# 3port-PicoUPS.net
KiCad netlist of a schematic drawn in EAGLE
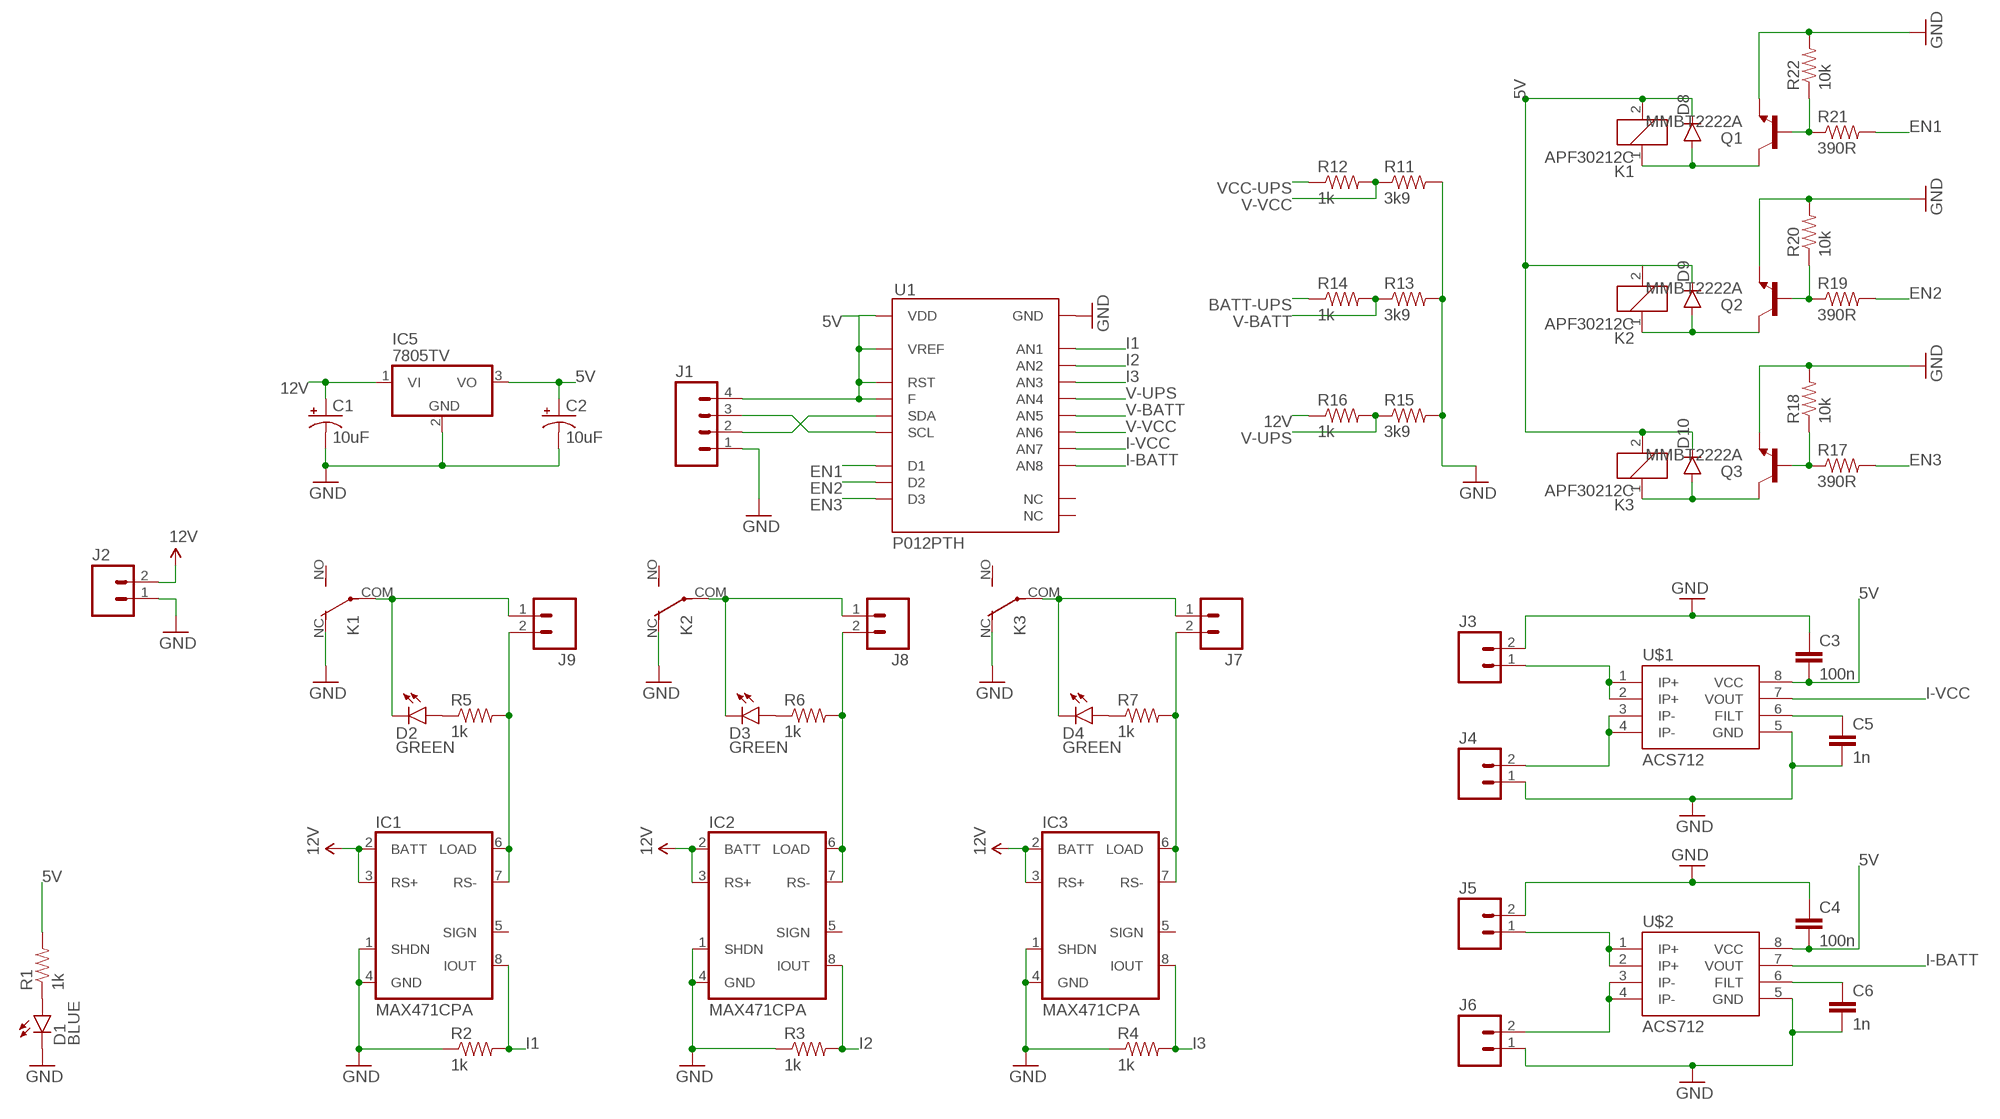
[diagram p0: schematic, sheet 1]

(export (version "E")
  (design (tool "Eeschema 10.0.6"))
  (components
    (comp (ref "C1")
      (value "10uF")
      (footprint "eagle-import:EIA3216")
      (libsource (lib "eagle-import") (part "10UF-16V-10%(TANT)"))
    )
    (comp (ref "C2")
      (value "10uF")
      (footprint "eagle-import:EIA3216")
      (libsource (lib "eagle-import") (part "10UF-16V-10%(TANT)"))
    )
    (comp (ref "C3")
      (value "100n")
      (footprint "eagle-import:0805")
      (libsource (lib "eagle-import") (part "CAP0805"))
    )
    (comp (ref "C4")
      (value "100n")
      (footprint "eagle-import:0805")
      (libsource (lib "eagle-import") (part "CAP0805"))
    )
    (comp (ref "C5")
      (value "1n")
      (footprint "eagle-import:0805")
      (libsource (lib "eagle-import") (part "CAP0805"))
    )
    (comp (ref "C6")
      (value "1n")
      (footprint "eagle-import:0805")
      (libsource (lib "eagle-import") (part "CAP0805"))
    )
    (comp (ref "D1")
      (value "BLUE")
      (footprint "eagle-import:LED-0603")
      (libsource (lib "eagle-import") (part "LED-BLUE0603"))
    )
    (comp (ref "D2")
      (value "GREEN")
      (footprint "eagle-import:LED-0603")
      (libsource (lib "eagle-import") (part "LED-GREEN0603"))
    )
    (comp (ref "D3")
      (value "GREEN")
      (footprint "eagle-import:LED-0603")
      (libsource (lib "eagle-import") (part "LED-GREEN0603"))
    )
    (comp (ref "D4")
      (value "GREEN")
      (footprint "eagle-import:LED-0603")
      (libsource (lib "eagle-import") (part "LED-GREEN0603"))
    )
    (comp (ref "D8")
      (value "DIODESOD123")
      (footprint "eagle-import:SOD-123")
      (libsource (lib "eagle-import") (part "DIODESOD123"))
    )
    (comp (ref "D9")
      (value "DIODESOD123")
      (footprint "eagle-import:SOD-123")
      (libsource (lib "eagle-import") (part "DIODESOD123"))
    )
    (comp (ref "D10")
      (value "DIODESOD123")
      (footprint "eagle-import:SOD-123")
      (libsource (lib "eagle-import") (part "DIODESOD123"))
    )
    (comp (ref "IC1")
      (value "MAX471CPA")
      (footprint "eagle-import:SO08")
      (libsource (lib "eagle-import") (part "MAX471CPA"))
    )
    (comp (ref "IC2")
      (value "MAX471CPA")
      (footprint "eagle-import:SO08")
      (libsource (lib "eagle-import") (part "MAX471CPA"))
    )
    (comp (ref "IC3")
      (value "MAX471CPA")
      (footprint "eagle-import:SO08")
      (libsource (lib "eagle-import") (part "MAX471CPA"))
    )
    (comp (ref "IC5")
      (value "7805TV")
      (footprint "eagle-import:TO220V")
      (libsource (lib "eagle-import") (part "78TV05"))
    )
    (comp (ref "J1")
      (value "M04PTH")
      (footprint "eagle-import:1X04")
      (libsource (lib "eagle-import") (part "M04PTH"))
    )
    (comp (ref "J2")
      (value "M025MM")
      (footprint "eagle-import:SCREWTERMINAL-5MM-2")
      (libsource (lib "eagle-import") (part "M025MM"))
    )
    (comp (ref "J3")
      (value "M025MM")
      (footprint "eagle-import:SCREWTERMINAL-5MM-2")
      (libsource (lib "eagle-import") (part "M025MM"))
    )
    (comp (ref "J4")
      (value "M025MM")
      (footprint "eagle-import:SCREWTERMINAL-5MM-2")
      (libsource (lib "eagle-import") (part "M025MM"))
    )
    (comp (ref "J5")
      (value "M025MM")
      (footprint "eagle-import:SCREWTERMINAL-5MM-2")
      (libsource (lib "eagle-import") (part "M025MM"))
    )
    (comp (ref "J6")
      (value "M025MM")
      (footprint "eagle-import:SCREWTERMINAL-5MM-2")
      (libsource (lib "eagle-import") (part "M025MM"))
    )
    (comp (ref "J7")
      (value "M025MM")
      (footprint "eagle-import:SCREWTERMINAL-5MM-2")
      (libsource (lib "eagle-import") (part "M025MM"))
    )
    (comp (ref "J8")
      (value "M025MM")
      (footprint "eagle-import:SCREWTERMINAL-5MM-2")
      (libsource (lib "eagle-import") (part "M025MM"))
    )
    (comp (ref "J9")
      (value "M025MM")
      (footprint "eagle-import:SCREWTERMINAL-5MM-2")
      (libsource (lib "eagle-import") (part "M025MM"))
    )
    (comp (ref "K1")
      (value "APF30212C")
      (footprint "eagle-import:APF30212C")
      (libsource (lib "eagle-import") (part "APF30212C"))
    )
    (comp (ref "K2")
      (value "APF30212C")
      (footprint "eagle-import:APF30212C")
      (libsource (lib "eagle-import") (part "APF30212C"))
    )
    (comp (ref "K3")
      (value "APF30212C")
      (footprint "eagle-import:APF30212C")
      (libsource (lib "eagle-import") (part "APF30212C"))
    )
    (comp (ref "Q1")
      (value "MMBT2222A")
      (footprint "eagle-import:SOT23-3")
      (libsource (lib "eagle-import") (part "TRANSISTOR_NPNMMBT2222A"))
    )
    (comp (ref "Q2")
      (value "MMBT2222A")
      (footprint "eagle-import:SOT23-3")
      (libsource (lib "eagle-import") (part "TRANSISTOR_NPNMMBT2222A"))
    )
    (comp (ref "Q3")
      (value "MMBT2222A")
      (footprint "eagle-import:SOT23-3")
      (libsource (lib "eagle-import") (part "TRANSISTOR_NPNMMBT2222A"))
    )
    (comp (ref "R1")
      (value "1k")
      (footprint "eagle-import:0805")
      (libsource (lib "eagle-import") (part "RESISTOR0805-RES"))
    )
    (comp (ref "R2")
      (value "1k")
      (footprint "eagle-import:0805")
      (libsource (lib "eagle-import") (part "RESISTOR0805-RES"))
    )
    (comp (ref "R3")
      (value "1k")
      (footprint "eagle-import:0805")
      (libsource (lib "eagle-import") (part "RESISTOR0805-RES"))
    )
    (comp (ref "R4")
      (value "1k")
      (footprint "eagle-import:0805")
      (libsource (lib "eagle-import") (part "RESISTOR0805-RES"))
    )
    (comp (ref "R5")
      (value "1k")
      (footprint "eagle-import:0805")
      (libsource (lib "eagle-import") (part "RESISTOR0805-RES"))
    )
    (comp (ref "R6")
      (value "1k")
      (footprint "eagle-import:0805")
      (libsource (lib "eagle-import") (part "RESISTOR0805-RES"))
    )
    (comp (ref "R7")
      (value "1k")
      (footprint "eagle-import:0805")
      (libsource (lib "eagle-import") (part "RESISTOR0805-RES"))
    )
    (comp (ref "R11")
      (value "3k9")
      (footprint "eagle-import:0805")
      (libsource (lib "eagle-import") (part "RESISTOR0805-RES"))
    )
    (comp (ref "R12")
      (value "1k")
      (footprint "eagle-import:0805")
      (libsource (lib "eagle-import") (part "RESISTOR0805-RES"))
    )
    (comp (ref "R13")
      (value "3k9")
      (footprint "eagle-import:0805")
      (libsource (lib "eagle-import") (part "RESISTOR0805-RES"))
    )
    (comp (ref "R14")
      (value "1k")
      (footprint "eagle-import:0805")
      (libsource (lib "eagle-import") (part "RESISTOR0805-RES"))
    )
    (comp (ref "R15")
      (value "3k9")
      (footprint "eagle-import:0805")
      (libsource (lib "eagle-import") (part "RESISTOR0805-RES"))
    )
    (comp (ref "R16")
      (value "1k")
      (footprint "eagle-import:0805")
      (libsource (lib "eagle-import") (part "RESISTOR0805-RES"))
    )
    (comp (ref "R17")
      (value "390R")
      (footprint "eagle-import:0805")
      (libsource (lib "eagle-import") (part "RESISTOR0805-RES"))
    )
    (comp (ref "R18")
      (value "10k")
      (footprint "eagle-import:0805")
      (libsource (lib "eagle-import") (part "RESISTOR0805-RES"))
    )
    (comp (ref "R19")
      (value "390R")
      (footprint "eagle-import:0805")
      (libsource (lib "eagle-import") (part "RESISTOR0805-RES"))
    )
    (comp (ref "R20")
      (value "10k")
      (footprint "eagle-import:0805")
      (libsource (lib "eagle-import") (part "RESISTOR0805-RES"))
    )
    (comp (ref "R21")
      (value "390R")
      (footprint "eagle-import:0805")
      (libsource (lib "eagle-import") (part "RESISTOR0805-RES"))
    )
    (comp (ref "R22")
      (value "10k")
      (footprint "eagle-import:0805")
      (libsource (lib "eagle-import") (part "RESISTOR0805-RES"))
    )
    (comp (ref "U$1")
      (value "ACS712")
      (footprint "eagle-import:SO08")
      (libsource (lib "eagle-import") (part "ACS712"))
    )
    (comp (ref "U$2")
      (value "ACS712")
      (footprint "eagle-import:SO08")
      (libsource (lib "eagle-import") (part "ACS712"))
    )
    (comp (ref "U1")
      (value "P012PTH")
      (footprint "eagle-import:DIL20")
      (libsource (lib "eagle-import") (part "P012PTH"))
    )
  )
  (nets
    (net (code "1") (name "/5V") (class "Default")
      (node (ref "C2") (pin "A") (pinfunction "+_A") (pintype "passive"))
      (node (ref "C3") (pin "2") (pinfunction "2_2") (pintype "passive"))
      (node (ref "C4") (pin "2") (pinfunction "2_2") (pintype "passive"))
      (node (ref "D10") (pin "C") (pinfunction "C_C") (pintype "passive"))
      (node (ref "D8") (pin "C") (pinfunction "C_C") (pintype "passive"))
      (node (ref "D9") (pin "C") (pinfunction "C_C") (pintype "passive"))
      (node (ref "IC5") (pin "3") (pinfunction "VO_3") (pintype "passive"))
      (node (ref "J1") (pin "4") (pinfunction "4_4") (pintype "passive"))
      (node (ref "K1") (pin "2") (pinfunction "2_2") (pintype "passive"))
      (node (ref "K2") (pin "2") (pinfunction "2_2") (pintype "passive"))
      (node (ref "K3") (pin "2") (pinfunction "2_2") (pintype "passive"))
      (node (ref "R1") (pin "2") (pinfunction "2_2") (pintype "passive"))
      (node (ref "U$1") (pin "8") (pinfunction "VCC_8") (pintype "bidirectional"))
      (node (ref "U$2") (pin "8") (pinfunction "VCC_8") (pintype "bidirectional"))
      (node (ref "U1") (pin "1") (pinfunction "VDD_1") (pintype "power_in"))
      (node (ref "U1") (pin "18") (pinfunction "VREF_18") (pintype "input"))
      (node (ref "U1") (pin "4") (pinfunction "RST_4") (pintype "input"))
      (node (ref "U1") (pin "9") (pinfunction "F_9") (pintype "input"))
    )
    (net (code "2") (name "/BATT-UPS") (class "Default")
      (node (ref "J6") (pin "2") (pinfunction "2_2") (pintype "passive"))
      (node (ref "R14") (pin "1") (pinfunction "1_1") (pintype "passive"))
      (node (ref "U$2") (pin "3") (pinfunction "IP-_3") (pintype "bidirectional"))
      (node (ref "U$2") (pin "4") (pinfunction "IP-_4") (pintype "bidirectional"))
    )
    (net (code "3") (name "/EN1") (class "Default")
      (node (ref "R21") (pin "2") (pinfunction "2_2") (pintype "passive"))
      (node (ref "U1") (pin "2") (pinfunction "D1_2") (pintype "output"))
    )
    (net (code "4") (name "/EN2") (class "Default")
      (node (ref "R19") (pin "2") (pinfunction "2_2") (pintype "passive"))
      (node (ref "U1") (pin "6") (pinfunction "D2_6") (pintype "output"))
    )
    (net (code "5") (name "/EN3") (class "Default")
      (node (ref "R17") (pin "2") (pinfunction "2_2") (pintype "passive"))
      (node (ref "U1") (pin "5") (pinfunction "D3_5") (pintype "output"))
    )
    (net (code "6") (name "/I-BATT") (class "Default")
      (node (ref "U$2") (pin "7") (pinfunction "VOUT_7") (pintype "bidirectional"))
      (node (ref "U1") (pin "19") (pinfunction "AN8_19") (pintype "input"))
    )
    (net (code "7") (name "/I-VCC") (class "Default")
      (node (ref "U$1") (pin "7") (pinfunction "VOUT_7") (pintype "bidirectional"))
      (node (ref "U1") (pin "17") (pinfunction "AN7_17") (pintype "input"))
    )
    (net (code "8") (name "/I1") (class "Default")
      (node (ref "IC1") (pin "8") (pinfunction "IOUT_8") (pintype "output"))
      (node (ref "R2") (pin "2") (pinfunction "2_2") (pintype "passive"))
      (node (ref "U1") (pin "3") (pinfunction "AN1_3") (pintype "input"))
    )
    (net (code "9") (name "/I2") (class "Default")
      (node (ref "IC2") (pin "8") (pinfunction "IOUT_8") (pintype "output"))
      (node (ref "R3") (pin "2") (pinfunction "2_2") (pintype "passive"))
      (node (ref "U1") (pin "7") (pinfunction "AN2_7") (pintype "input"))
    )
    (net (code "10") (name "/I3") (class "Default")
      (node (ref "IC3") (pin "8") (pinfunction "IOUT_8") (pintype "output"))
      (node (ref "R4") (pin "2") (pinfunction "2_2") (pintype "passive"))
      (node (ref "U1") (pin "8") (pinfunction "AN3_8") (pintype "input"))
    )
    (net (code "11") (name "/V-BATT") (class "Default")
      (node (ref "R13") (pin "1") (pinfunction "1_1") (pintype "passive"))
      (node (ref "R14") (pin "2") (pinfunction "2_2") (pintype "passive"))
      (node (ref "U1") (pin "15") (pinfunction "AN5_15") (pintype "input"))
    )
    (net (code "12") (name "/V-UPS") (class "Default")
      (node (ref "R15") (pin "1") (pinfunction "1_1") (pintype "passive"))
      (node (ref "R16") (pin "2") (pinfunction "2_2") (pintype "passive"))
      (node (ref "U1") (pin "14") (pinfunction "AN4_14") (pintype "input"))
    )
    (net (code "13") (name "/V-VCC") (class "Default")
      (node (ref "R11") (pin "1") (pinfunction "1_1") (pintype "passive"))
      (node (ref "R12") (pin "2") (pinfunction "2_2") (pintype "passive"))
      (node (ref "U1") (pin "16") (pinfunction "AN6_16") (pintype "input"))
    )
    (net (code "14") (name "/VCC-UPS") (class "Default")
      (node (ref "J4") (pin "2") (pinfunction "2_2") (pintype "passive"))
      (node (ref "R12") (pin "1") (pinfunction "1_1") (pintype "passive"))
      (node (ref "U$1") (pin "3") (pinfunction "IP-_3") (pintype "bidirectional"))
      (node (ref "U$1") (pin "4") (pinfunction "IP-_4") (pintype "bidirectional"))
    )
    (net (code "15") (name "12V") (class "Default")
      (node (ref "C1") (pin "A") (pinfunction "+_A") (pintype "passive"))
      (node (ref "IC1") (pin "2") (pinfunction "BATT_2") (pintype "input"))
      (node (ref "IC1") (pin "3") (pinfunction "RS+_3") (pintype "input"))
      (node (ref "IC2") (pin "2") (pinfunction "BATT_2") (pintype "input"))
      (node (ref "IC2") (pin "3") (pinfunction "RS+_3") (pintype "input"))
      (node (ref "IC3") (pin "2") (pinfunction "BATT_2") (pintype "input"))
      (node (ref "IC3") (pin "3") (pinfunction "RS+_3") (pintype "input"))
      (node (ref "IC5") (pin "1") (pinfunction "VI_1") (pintype "input"))
      (node (ref "J2") (pin "2") (pinfunction "2_2") (pintype "passive"))
      (node (ref "R16") (pin "1") (pinfunction "1_1") (pintype "passive"))
    )
    (net (code "16") (name "GND") (class "Default")
      (node (ref "C1") (pin "C") (pinfunction "-_C") (pintype "passive"))
      (node (ref "C2") (pin "C") (pinfunction "-_C") (pintype "passive"))
      (node (ref "C3") (pin "1") (pinfunction "1_1") (pintype "passive"))
      (node (ref "C4") (pin "1") (pinfunction "1_1") (pintype "passive"))
      (node (ref "C5") (pin "2") (pinfunction "2_2") (pintype "passive"))
      (node (ref "C6") (pin "2") (pinfunction "2_2") (pintype "passive"))
      (node (ref "D1") (pin "C") (pinfunction "C_C") (pintype "passive"))
      (node (ref "IC1") (pin "1") (pinfunction "SHDN_1") (pintype "input"))
      (node (ref "IC1") (pin "4") (pinfunction "GND_4") (pintype "power_in"))
      (node (ref "IC2") (pin "1") (pinfunction "SHDN_1") (pintype "input"))
      (node (ref "IC2") (pin "4") (pinfunction "GND_4") (pintype "power_in"))
      (node (ref "IC3") (pin "1") (pinfunction "SHDN_1") (pintype "input"))
      (node (ref "IC3") (pin "4") (pinfunction "GND_4") (pintype "power_in"))
      (node (ref "IC5") (pin "2") (pinfunction "GND_2") (pintype "passive"))
      (node (ref "J1") (pin "1") (pinfunction "1_1") (pintype "passive"))
      (node (ref "J2") (pin "1") (pinfunction "1_1") (pintype "passive"))
      (node (ref "J3") (pin "2") (pinfunction "2_2") (pintype "passive"))
      (node (ref "J4") (pin "1") (pinfunction "1_1") (pintype "passive"))
      (node (ref "J5") (pin "2") (pinfunction "2_2") (pintype "passive"))
      (node (ref "J6") (pin "1") (pinfunction "1_1") (pintype "passive"))
      (node (ref "K1") (pin "NC") (pinfunction "O_NC") (pintype "passive"))
      (node (ref "K2") (pin "NC") (pinfunction "O_NC") (pintype "passive"))
      (node (ref "K3") (pin "NC") (pinfunction "O_NC") (pintype "passive"))
      (node (ref "Q1") (pin "2") (pinfunction "E_2") (pintype "passive"))
      (node (ref "Q2") (pin "2") (pinfunction "E_2") (pintype "passive"))
      (node (ref "Q3") (pin "2") (pinfunction "E_2") (pintype "passive"))
      (node (ref "R11") (pin "2") (pinfunction "2_2") (pintype "passive"))
      (node (ref "R13") (pin "2") (pinfunction "2_2") (pintype "passive"))
      (node (ref "R15") (pin "2") (pinfunction "2_2") (pintype "passive"))
      (node (ref "R18") (pin "2") (pinfunction "2_2") (pintype "passive"))
      (node (ref "R2") (pin "1") (pinfunction "1_1") (pintype "passive"))
      (node (ref "R20") (pin "2") (pinfunction "2_2") (pintype "passive"))
      (node (ref "R22") (pin "2") (pinfunction "2_2") (pintype "passive"))
      (node (ref "R3") (pin "1") (pinfunction "1_1") (pintype "passive"))
      (node (ref "R4") (pin "1") (pinfunction "1_1") (pintype "passive"))
      (node (ref "U$1") (pin "5") (pinfunction "GND_5") (pintype "bidirectional"))
      (node (ref "U$2") (pin "5") (pinfunction "GND_5") (pintype "bidirectional"))
      (node (ref "U1") (pin "20") (pinfunction "GND_20") (pintype "power_in"))
    )
    (net (code "17") (name "Net-(D1-PadA)") (class "Default")
      (node (ref "D1") (pin "A") (pinfunction "A_A") (pintype "passive"))
      (node (ref "R1") (pin "1") (pinfunction "1_1") (pintype "passive"))
    )
    (net (code "18") (name "Net-(D2-PadA)") (class "Default")
      (node (ref "D2") (pin "A") (pinfunction "A_A") (pintype "passive"))
      (node (ref "R5") (pin "1") (pinfunction "1_1") (pintype "passive"))
    )
    (net (code "19") (name "Net-(D3-PadA)") (class "Default")
      (node (ref "D3") (pin "A") (pinfunction "A_A") (pintype "passive"))
      (node (ref "R6") (pin "1") (pinfunction "1_1") (pintype "passive"))
    )
    (net (code "20") (name "Net-(D4-PadA)") (class "Default")
      (node (ref "D4") (pin "A") (pinfunction "A_A") (pintype "passive"))
      (node (ref "R7") (pin "1") (pinfunction "1_1") (pintype "passive"))
    )
    (net (code "21") (name "Net-(IC1-LOAD)") (class "Default")
      (node (ref "IC1") (pin "6") (pinfunction "LOAD_6") (pintype "output"))
      (node (ref "IC1") (pin "7") (pinfunction "RS-_7") (pintype "input"))
      (node (ref "J9") (pin "2") (pinfunction "2_2") (pintype "passive"))
      (node (ref "R5") (pin "2") (pinfunction "2_2") (pintype "passive"))
    )
    (net (code "22") (name "Net-(IC2-LOAD)") (class "Default")
      (node (ref "IC2") (pin "6") (pinfunction "LOAD_6") (pintype "output"))
      (node (ref "IC2") (pin "7") (pinfunction "RS-_7") (pintype "input"))
      (node (ref "J8") (pin "2") (pinfunction "2_2") (pintype "passive"))
      (node (ref "R6") (pin "2") (pinfunction "2_2") (pintype "passive"))
    )
    (net (code "23") (name "Net-(IC3-LOAD)") (class "Default")
      (node (ref "IC3") (pin "6") (pinfunction "LOAD_6") (pintype "output"))
      (node (ref "IC3") (pin "7") (pinfunction "RS-_7") (pintype "input"))
      (node (ref "J7") (pin "2") (pinfunction "2_2") (pintype "passive"))
      (node (ref "R7") (pin "2") (pinfunction "2_2") (pintype "passive"))
    )
    (net (code "24") (name "Net-(J3-Pad1)") (class "Default")
      (node (ref "J3") (pin "1") (pinfunction "1_1") (pintype "passive"))
      (node (ref "U$1") (pin "1") (pinfunction "IP+_1") (pintype "bidirectional"))
      (node (ref "U$1") (pin "2") (pinfunction "IP+_2") (pintype "bidirectional"))
    )
    (net (code "25") (name "Net-(J5-Pad1)") (class "Default")
      (node (ref "J5") (pin "1") (pinfunction "1_1") (pintype "passive"))
      (node (ref "U$2") (pin "1") (pinfunction "IP+_1") (pintype "bidirectional"))
      (node (ref "U$2") (pin "2") (pinfunction "IP+_2") (pintype "bidirectional"))
    )
    (net (code "26") (name "Net-(K1B-P)") (class "Default")
      (node (ref "D2") (pin "C") (pinfunction "C_C") (pintype "passive"))
      (node (ref "J9") (pin "1") (pinfunction "1_1") (pintype "passive"))
      (node (ref "K1") (pin "COM") (pinfunction "P_COM") (pintype "passive"))
    )
    (net (code "27") (name "Net-(K2B-P)") (class "Default")
      (node (ref "D3") (pin "C") (pinfunction "C_C") (pintype "passive"))
      (node (ref "J8") (pin "1") (pinfunction "1_1") (pintype "passive"))
      (node (ref "K2") (pin "COM") (pinfunction "P_COM") (pintype "passive"))
    )
    (net (code "28") (name "Net-(K3B-P)") (class "Default")
      (node (ref "D4") (pin "C") (pinfunction "C_C") (pintype "passive"))
      (node (ref "J7") (pin "1") (pinfunction "1_1") (pintype "passive"))
      (node (ref "K3") (pin "COM") (pinfunction "P_COM") (pintype "passive"))
    )
    (net (code "29") (name "Net-(Q1-B)") (class "Default")
      (node (ref "Q1") (pin "1") (pinfunction "B_1") (pintype "passive"))
      (node (ref "R21") (pin "1") (pinfunction "1_1") (pintype "passive"))
      (node (ref "R22") (pin "1") (pinfunction "1_1") (pintype "passive"))
    )
    (net (code "30") (name "Net-(Q1-C)") (class "Default")
      (node (ref "D8") (pin "A") (pinfunction "A_A") (pintype "passive"))
      (node (ref "K1") (pin "1") (pinfunction "1_1") (pintype "passive"))
      (node (ref "Q1") (pin "3") (pinfunction "C_3") (pintype "passive"))
    )
    (net (code "31") (name "Net-(Q2-B)") (class "Default")
      (node (ref "Q2") (pin "1") (pinfunction "B_1") (pintype "passive"))
      (node (ref "R19") (pin "1") (pinfunction "1_1") (pintype "passive"))
      (node (ref "R20") (pin "1") (pinfunction "1_1") (pintype "passive"))
    )
    (net (code "32") (name "Net-(Q2-C)") (class "Default")
      (node (ref "D9") (pin "A") (pinfunction "A_A") (pintype "passive"))
      (node (ref "K2") (pin "1") (pinfunction "1_1") (pintype "passive"))
      (node (ref "Q2") (pin "3") (pinfunction "C_3") (pintype "passive"))
    )
    (net (code "33") (name "Net-(Q3-B)") (class "Default")
      (node (ref "Q3") (pin "1") (pinfunction "B_1") (pintype "passive"))
      (node (ref "R17") (pin "1") (pinfunction "1_1") (pintype "passive"))
      (node (ref "R18") (pin "1") (pinfunction "1_1") (pintype "passive"))
    )
    (net (code "34") (name "Net-(Q3-C)") (class "Default")
      (node (ref "D10") (pin "A") (pinfunction "A_A") (pintype "passive"))
      (node (ref "K3") (pin "1") (pinfunction "1_1") (pintype "passive"))
      (node (ref "Q3") (pin "3") (pinfunction "C_3") (pintype "passive"))
    )
    (net (code "35") (name "Net-(U$1-FILT)") (class "Default")
      (node (ref "C5") (pin "1") (pinfunction "1_1") (pintype "passive"))
      (node (ref "U$1") (pin "6") (pinfunction "FILT_6") (pintype "bidirectional"))
    )
    (net (code "36") (name "Net-(U$2-FILT)") (class "Default")
      (node (ref "C6") (pin "1") (pinfunction "1_1") (pintype "passive"))
      (node (ref "U$2") (pin "6") (pinfunction "FILT_6") (pintype "bidirectional"))
    )
    (net (code "37") (name "Net-(U1-SCL)") (class "Default")
      (node (ref "J1") (pin "3") (pinfunction "3_3") (pintype "passive"))
      (node (ref "U1") (pin "11") (pinfunction "SCL_11") (pintype "input"))
    )
    (net (code "38") (name "Net-(U1-SDA)") (class "Default")
      (node (ref "J1") (pin "2") (pinfunction "2_2") (pintype "passive"))
      (node (ref "U1") (pin "13") (pinfunction "SDA_13") (pintype "input"))
    )
    (net (code "39") (name "unconnected-(IC1-SIGN-Pad5)") (class "Default")
      (node (ref "IC1") (pin "5") (pinfunction "SIGN_5") (pintype "open_collector"))
    )
    (net (code "40") (name "unconnected-(IC2-SIGN-Pad5)") (class "Default")
      (node (ref "IC2") (pin "5") (pinfunction "SIGN_5") (pintype "open_collector"))
    )
    (net (code "41") (name "unconnected-(IC3-SIGN-Pad5)") (class "Default")
      (node (ref "IC3") (pin "5") (pinfunction "SIGN_5") (pintype "open_collector"))
    )
    (net (code "42") (name "unconnected-(K1B-S-PadNO)") (class "Default")
      (node (ref "K1") (pin "NO") (pinfunction "S_NO") (pintype "passive"))
    )
    (net (code "43") (name "unconnected-(K2B-S-PadNO)") (class "Default")
      (node (ref "K2") (pin "NO") (pinfunction "S_NO") (pintype "passive"))
    )
    (net (code "44") (name "unconnected-(K3B-S-PadNO)") (class "Default")
      (node (ref "K3") (pin "NO") (pinfunction "S_NO") (pintype "passive"))
    )
    (net (code "45") (name "unconnected-(U1-NC-Pad10)") (class "Default")
      (node (ref "U1") (pin "10") (pinfunction "NC_10") (pintype "no_connect"))
    )
    (net (code "46") (name "unconnected-(U1-NC-Pad12)") (class "Default")
      (node (ref "U1") (pin "12") (pinfunction "NC_12") (pintype "no_connect"))
    )
  )
)
